# MCU.net
KiCad netlist of a schematic drawn in Altium Designer
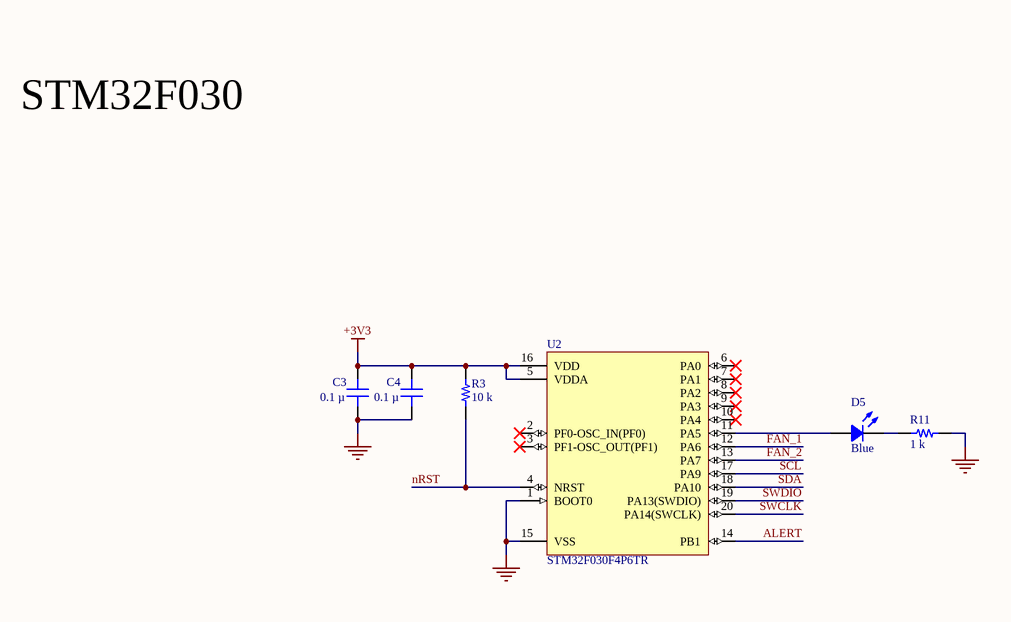
[diagram p0: MCU.SchDoc]

(export (version "E")
  (design (tool "Eeschema 10.0.6"))
  (components
    (comp (ref "C3")
      (value "0.1 µ")
      (footprint "CAP 0603_1608")
      (description "CAP CER 0.1UF 50V X7R 0603")
      (fields (field (name "PART NUMBER") "C0603C104K5RAC7411") (field (name "MANUFACTURER") "KEMET"))
      (libsource (lib "Celestial Altium Library - altium_library") (part "Capacitor"))
    )
    (comp (ref "C4")
      (value "0.1 µ")
      (footprint "CAP 0603_1608")
      (description "CAP CER 0.1UF 50V X7R 0603")
      (fields (field (name "PART NUMBER") "C0603C104K5RAC7411") (field (name "MANUFACTURER") "KEMET"))
      (libsource (lib "Celestial Altium Library - altium_library") (part "Capacitor"))
    )
    (comp (ref "D5")
      (value "Blue")
      (footprint "LED 0603_1608 BLUE")
      (description "LED BLUE CLEAR CHIP SMD")
      (fields (field (name "PART NUMBER") "LTST-C190TBKT") (field (name "MANUFACTURER") "Lite-On Inc."))
      (libsource (lib "Celestial Altium Library - altium_library") (part "LED"))
    )
    (comp (ref "R3")
      (value "10 k")
      (footprint "RES 0603_1608")
      (description "RES 10K OHM 0.1% 1/16W 0603")
      (fields
        (field (name "PART NUMBER") "RNCS0603BKE10K0")
        (field (name "MANUFACTURER") "Stackpole Electronics Inc")
      )
      (libsource (lib "Celestial Altium Library - altium_library") (part "Resistor"))
    )
    (comp (ref "R11")
      (value "1 k")
      (footprint "RES 0603_1608")
      (description "RES SMD 1K OHM 0.1% 1/16W 0603")
      (fields
        (field (name "PART NUMBER") "CPF0603B1K0E")
        (field (name "MANUFACTURER") "TE Connectivity Passive Product")
      )
      (libsource (lib "Celestial Altium Library - altium_library") (part "Resistor"))
    )
    (comp (ref "U2")
      (value "STM32F030F4P6TR")
      (footprint "STM-TSSOP20_M")
      (description "RISC Microcontroller, 32-Bit, FLASH, CORTEX-M0 CPU, 48MHz, CMOS, PDSO20")
      (libsource (lib "University of South Florida") (part "MC-ARM-STM32F030-TSSOP20"))
    )
  )
  (nets
    (net (code "1") (name "+3V3") (class "Default")
      (node (ref "C3") (pin "2") (pinfunction "2_2") (pintype "passive"))
      (node (ref "C4") (pin "2") (pinfunction "2_2") (pintype "passive"))
      (node (ref "R3") (pin "2") (pinfunction "2_2") (pintype "passive"))
      (node (ref "U2") (pin "16") (pinfunction "VDD_16") (pintype "power_in"))
      (node (ref "U2") (pin "5") (pinfunction "VDDA_5") (pintype "power_in"))
    )
    (net (code "2") (name "/ALERT") (class "Default")
      (node (ref "U2") (pin "14") (pinfunction "PB1_14") (pintype "bidirectional"))
    )
    (net (code "3") (name "/FAN_1") (class "Default")
      (node (ref "U2") (pin "12") (pinfunction "PA6_12") (pintype "bidirectional"))
    )
    (net (code "4") (name "/FAN_2") (class "Default")
      (node (ref "U2") (pin "13") (pinfunction "PA7_13") (pintype "bidirectional"))
    )
    (net (code "5") (name "/SCL") (class "Default")
      (node (ref "U2") (pin "17") (pinfunction "PA9_17") (pintype "bidirectional"))
    )
    (net (code "6") (name "/SDA") (class "Default")
      (node (ref "U2") (pin "18") (pinfunction "PA10_18") (pintype "bidirectional"))
    )
    (net (code "7") (name "/SWCLK") (class "Default")
      (node (ref "U2") (pin "20") (pinfunction "PA14(SWCLK)_20") (pintype "bidirectional"))
    )
    (net (code "8") (name "/SWDIO") (class "Default")
      (node (ref "U2") (pin "19") (pinfunction "PA13(SWDIO)_19") (pintype "bidirectional"))
    )
    (net (code "9") (name "/nRST") (class "Default")
      (node (ref "R3") (pin "1") (pinfunction "1_1") (pintype "passive"))
      (node (ref "U2") (pin "4") (pinfunction "NRST_4") (pintype "bidirectional"))
    )
    (net (code "10") (name "GND") (class "Default")
      (node (ref "C3") (pin "1") (pinfunction "1_1") (pintype "passive"))
      (node (ref "C4") (pin "1") (pinfunction "1_1") (pintype "passive"))
      (node (ref "R11") (pin "2") (pinfunction "2_2") (pintype "passive"))
      (node (ref "U2") (pin "1") (pinfunction "BOOT0_1") (pintype "input"))
      (node (ref "U2") (pin "15") (pinfunction "VSS_15") (pintype "power_in"))
    )
    (net (code "11") (name "Net-(D5-Pad2)") (class "Default")
      (node (ref "D5") (pin "2") (pinfunction "2_2") (pintype "passive"))
      (node (ref "R11") (pin "1") (pinfunction "1_1") (pintype "passive"))
    )
    (net (code "12") (name "Net-(U2-PA5)") (class "Default")
      (node (ref "D5") (pin "1") (pinfunction "1_1") (pintype "passive"))
      (node (ref "U2") (pin "11") (pinfunction "PA5_11") (pintype "bidirectional"))
    )
    (net (code "13") (name "unconnected-(U2-PA0-Pad6)") (class "Default")
      (node (ref "U2") (pin "6") (pinfunction "PA0_6") (pintype "bidirectional+no_connect"))
    )
    (net (code "14") (name "unconnected-(U2-PA1-Pad7)") (class "Default")
      (node (ref "U2") (pin "7") (pinfunction "PA1_7") (pintype "bidirectional+no_connect"))
    )
    (net (code "15") (name "unconnected-(U2-PA2-Pad8)") (class "Default")
      (node (ref "U2") (pin "8") (pinfunction "PA2_8") (pintype "bidirectional+no_connect"))
    )
    (net (code "16") (name "unconnected-(U2-PA3-Pad9)") (class "Default")
      (node (ref "U2") (pin "9") (pinfunction "PA3_9") (pintype "bidirectional+no_connect"))
    )
    (net (code "17") (name "unconnected-(U2-PA4-Pad10)") (class "Default")
      (node (ref "U2") (pin "10") (pinfunction "PA4_10") (pintype "bidirectional+no_connect"))
    )
    (net (code "18") (name "unconnected-(U2-PF0-OSC_IN(PF0)-Pad2)") (class "Default")
      (node (ref "U2") (pin "2") (pinfunction "PF0-OSC_IN(PF0)_2") (pintype "bidirectional+no_connect"))
    )
    (net (code "19") (name "unconnected-(U2-PF1-OSC_OUT(PF1)-Pad3)") (class "Default")
      (node (ref "U2") (pin "3") (pinfunction "PF1-OSC_OUT(PF1)_3") (pintype "bidirectional+no_connect"))
    )
  )
)
